# Power_Sensors.net
KiCad netlist of a schematic drawn in Altium Designer
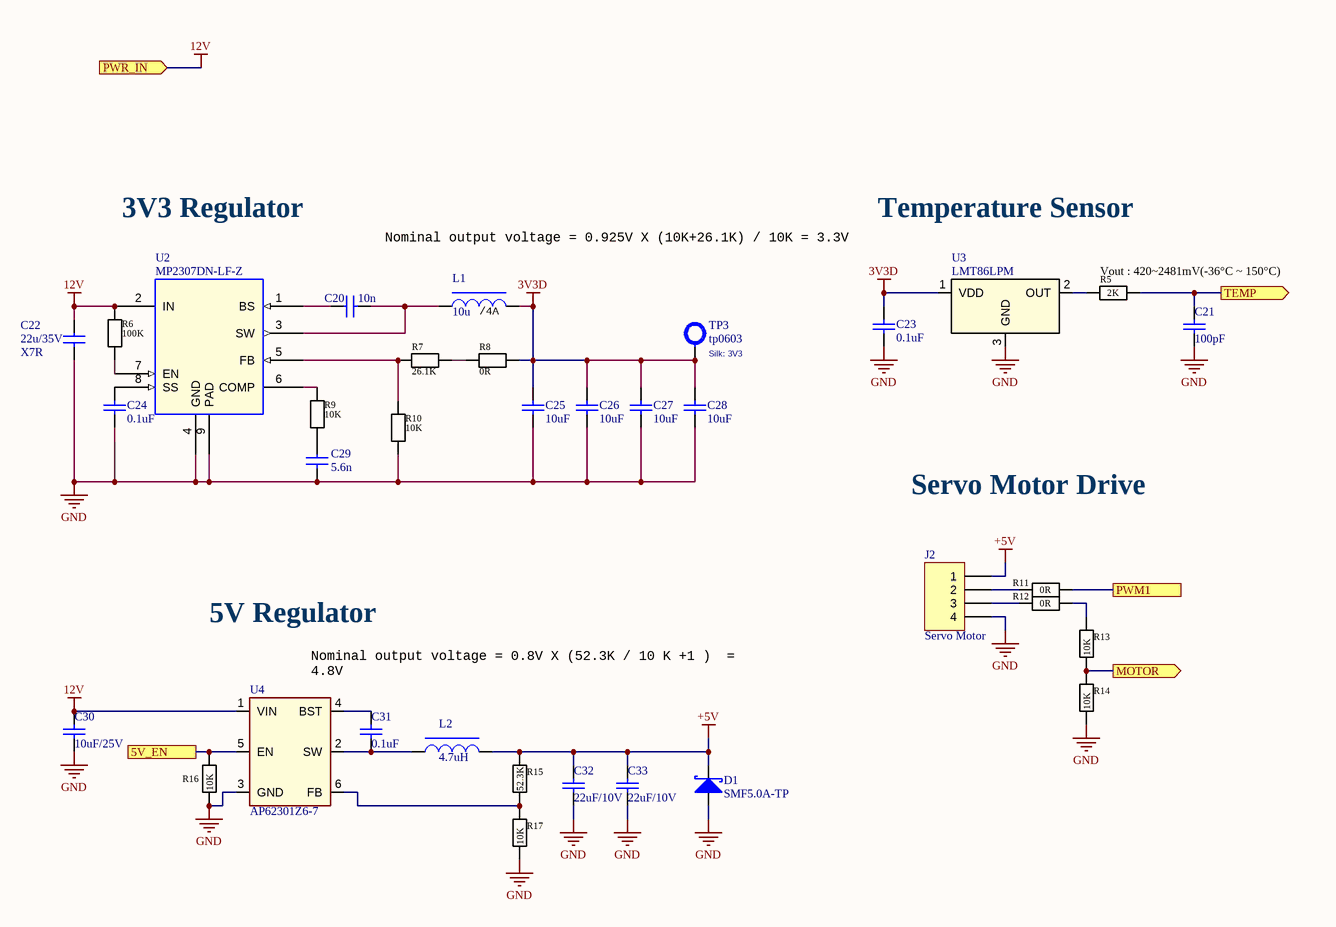
[diagram p0: Power,Sensors.SchDoc]

(export (version "E")
  (design (tool "Eeschema 10.0.6"))
  (components
    (comp (ref "C20")
      (value "10n")
      (footprint "CAPC1005X55USR")
      (description "CAP CER 10000PF 25V X7R 0402")
      (fields
        (field (name "DIGI-KEY PART NUMBER") "490-6340-2-ND")
        (field (name "MANUFACTURER") "Murata Electronics")
      )
      (libsource (lib "AA-Design-Challenge") (part "capacitor"))
    )
    (comp (ref "C21")
      (value "100pF")
      (footprint "CAPC1005X61USR")
      (description "CAP CER 100PF 50V C0G/NP0 0402")
      (fields
        (field (name "MANUFACTURER") "Murata Electronics")
        (field (name "MANUFACTURER PART NUMBER") "GCM1555C1H101FA16D")
      )
      (libsource (lib "AA-Design-Challenge") (part "Cap"))
    )
    (comp (ref "C22")
      (value "22u/35V")
      (footprint "CAPC3216X175USR")
      (description "CAP CER 22UF 35V JB 1206")
      (fields
        (field (name "MATERIAL") "X7R")
        (field (name "MANUFACTURER PART NUMBER") "C3216JB1V226M160AC")
        (field (name "MANUFACTURER") "TDK Corporation")
      )
      (libsource (lib "AA-Design-Challenge") (part "capacitor"))
    )
    (comp (ref "C23")
      (value "0.1uF")
      (footprint "CAPC1005X61USR")
      (description "CAP CER 0.1UF 50V X7R 0402")
      (fields
        (field (name "MANUFACTURER") "TDK Corporation")
        (field (name "MANUFACTURER PART NUMBER") "CGA2B3X7R1H104K050BB")
      )
      (libsource (lib "AA-Design-Challenge") (part "Cap"))
    )
    (comp (ref "C24")
      (value "0.1uF")
      (footprint "CAPC1005X61USR")
      (description "CAP CER 0.1UF 50V X7R 0402")
      (fields
        (field (name "MANUFACTURER") "TDK Corporation")
        (field (name "MANUFACTURER PART NUMBER") "CGA2B3X7R1H104K050BB")
      )
      (libsource (lib "AA-Design-Challenge") (part "Cap"))
    )
    (comp (ref "C25")
      (value "10uF")
      (footprint "CAPC1005X61USR")
      (description "CAP CER 10UF 10V X5R 0402")
      (fields
        (field (name "MANUFACTURER") "Samsung Electro-Mechanics")
        (field (name "MANUFACTURER PART NUMBER") "CL05A106MP8NUB8")
      )
      (libsource (lib "AA-Design-Challenge") (part "Cap"))
    )
    (comp (ref "C26")
      (value "10uF")
      (footprint "CAPC1005X61USR")
      (description "CAP CER 10UF 10V X5R 0402")
      (fields
        (field (name "MANUFACTURER") "Samsung Electro-Mechanics")
        (field (name "MANUFACTURER PART NUMBER") "CL05A106MP8NUB8")
      )
      (libsource (lib "AA-Design-Challenge") (part "Cap"))
    )
    (comp (ref "C27")
      (value "10uF")
      (footprint "CAPC1005X61USR")
      (description "CAP CER 10UF 10V X5R 0402")
      (fields
        (field (name "MANUFACTURER") "Samsung Electro-Mechanics")
        (field (name "MANUFACTURER PART NUMBER") "CL05A106MP8NUB8")
      )
      (libsource (lib "AA-Design-Challenge") (part "Cap"))
    )
    (comp (ref "C28")
      (value "10uF")
      (footprint "CAPC1005X61USR")
      (description "CAP CER 10UF 10V X5R 0402")
      (fields
        (field (name "MANUFACTURER") "Samsung Electro-Mechanics")
        (field (name "MANUFACTURER PART NUMBER") "CL05A106MP8NUB8")
      )
      (libsource (lib "AA-Design-Challenge") (part "Cap"))
    )
    (comp (ref "C29")
      (value "5.6n")
      (footprint "CAPC1005X55USR")
      (description "CAP CER 5600PF 50V X7R 0402")
      (fields
        (field (name "DIGI-KEY PART NUMBER") "490-6364-2-ND")
        (field (name "MANUFACTURER") "Murata Electronics")
      )
      (libsource (lib "AA-Design-Challenge") (part "capacitor"))
    )
    (comp (ref "C30")
      (value "10uF/25V")
      (footprint "CAPC2012X145USR")
      (description "CAP CER 10UF 25V X5R 0805")
      (fields
        (field (name "MANUFACTURER") "TDK Corporation")
        (field (name "MANUFACTURER PART NUMBER") "C2012X5R1E106K125AB")
      )
      (libsource (lib "AA-Design-Challenge") (part "Cap"))
    )
    (comp (ref "C31")
      (value "0.1uF")
      (footprint "CAPC1005X61USR")
      (description "CAP CER 0.1UF 50V X7R 0402")
      (fields
        (field (name "MANUFACTURER") "TDK Corporation")
        (field (name "MANUFACTURER PART NUMBER") "CGA2B3X7R1H104K050BB")
      )
      (libsource (lib "AA-Design-Challenge") (part "Cap"))
    )
    (comp (ref "C32")
      (value "22uF/10V")
      (footprint "CAPC2012X145USR")
      (description "CAP CER 22UF 10V X5R 0805")
      (fields
        (field (name "MANUFACTURER") "Samsung")
        (field (name "MANUFACTURER PART NUMBER") "CL21A226KPCLRNC")
      )
      (libsource (lib "AA-Design-Challenge") (part "Cap"))
    )
    (comp (ref "C33")
      (value "22uF/10V")
      (footprint "CAPC2012X145USR")
      (description "CAP CER 22UF 10V X5R 0805")
      (fields
        (field (name "MANUFACTURER") "Samsung")
        (field (name "MANUFACTURER PART NUMBER") "CL21A226KPCLRNC")
      )
      (libsource (lib "AA-Design-Challenge") (part "Cap"))
    )
    (comp (ref "D1")
      (value "SMF5.0A-TP")
      (footprint "SOD123FL")
      (description "TVS DIODE 5VWM 9.2VC SOD123FL")
      (fields (field (name "MANUFACTURER") "Micro Commercial Co"))
      (libsource (lib "AA-Design-Challenge") (part "SMF5.0A-TP"))
    )
    (comp (ref "J2")
      (value "Servo Motor")
      (footprint "4 pin 2.54 mm Breakaway")
      (description "Header, 4-Pin")
      (libsource (lib "AA-Design-Challenge") (part "Header 4"))
    )
    (comp (ref "L1")
      (value "10u")
      (footprint "IND_0630CDMCCDS_SUM")
      (description "FIXED IND 10UH 4A 67 MOHM SMD")
      (fields (field (name "DIGI-KEY PART NUMBER") "308-2459-2-ND") (field (name "VOLTAGE") "V"))
      (libsource (lib "AA-Design-Challenge") (part "inductor"))
    )
    (comp (ref "L2")
      (value "4.7uH")
      (footprint "IND_NR5040")
      (description "FIXED IND 4.7UH 3.1A 37.7MOHM SM")
      (fields
        (field (name "DIGI-KEY PART NUMBER") "587-2373-2-ND")
        (field (name "MANUFACTURER") "Taiyo Yuden")
      )
      (libsource (lib "AA-Design-Challenge") (part "inductor"))
    )
    (comp (ref "R5")
      (value "2K")
      (footprint "RESC1005X40USR")
      (description "RES SMD 2K OHM 1% 1/16W 0402")
      (fields
        (field (name "MANUFACTURER") "Yageo")
        (field (name "MANUFACTURER PART NUMBER") "RC0402FR-072KL")
      )
      (libsource (lib "AA-Design-Challenge") (part "R"))
    )
    (comp (ref "R6")
      (value "100K")
      (footprint "RESC1005X40USR")
      (description "RES SMD 100K OHM 1% 1/16W 0402")
      (fields
        (field (name "MANUFACTURER") "Yageo")
        (field (name "MANUFACTURER PART NUMBER") "RC0402FR-07100KL")
      )
      (libsource (lib "") (part "R_2"))
    )
    (comp (ref "R7")
      (value "26.1K")
      (footprint "RESC1005X40USR")
      (description "RES SMD 26.1K OHM 1% 1/5W 0402")
      (fields
        (field (name "MANUFACTURER") "Vishay Dale")
        (field (name "MANUFACTURER PART NUMBER") "CRCW040226K1FKEDHP")
      )
      (libsource (lib "AA-Design-Challenge") (part "R"))
    )
    (comp (ref "R8")
      (value "0R")
      (footprint "RESC1005X40USR")
      (description "RES SMD 0 OHM JUMPER 1/16W 0402")
      (fields
        (field (name "MANUFACTURER") "Yageo")
        (field (name "MANUFACTURER PART NUMBER") "RC0402FR-070RL")
      )
      (libsource (lib "AA-Design-Challenge") (part "R"))
    )
    (comp (ref "R9")
      (value "10K")
      (footprint "RESC1005X40USR")
      (description "RES 10K OHM 1% 1/16W 0402")
      (fields
        (field (name "MANUFACTURER") "Stackpole Electronics Inc")
        (field (name "MANUFACTURER PART NUMBER") "RMCF0402FT10K0")
      )
      (libsource (lib "") (part "R_2"))
    )
    (comp (ref "R10")
      (value "10K")
      (footprint "RESC1005X40USR")
      (description "RES 10K OHM 1% 1/16W 0402")
      (fields
        (field (name "MANUFACTURER") "Stackpole Electronics Inc")
        (field (name "MANUFACTURER PART NUMBER") "RMCF0402FT10K0")
      )
      (libsource (lib "") (part "R_2"))
    )
    (comp (ref "R11")
      (value "0R")
      (footprint "RESC1005X40USR")
      (description "RES SMD 0 OHM JUMPER 1/16W 0402")
      (fields
        (field (name "MANUFACTURER") "Yageo")
        (field (name "MANUFACTURER PART NUMBER") "RC0402FR-070RL")
      )
      (libsource (lib "AA-Design-Challenge") (part "R"))
    )
    (comp (ref "R12")
      (value "0R")
      (footprint "RESC1005X40USR")
      (description "RES SMD 0 OHM JUMPER 1/16W 0402")
      (fields
        (field (name "MANUFACTURER") "Yageo")
        (field (name "MANUFACTURER PART NUMBER") "RC0402FR-070RL")
      )
      (libsource (lib "AA-Design-Challenge") (part "R"))
    )
    (comp (ref "R13")
      (value "10K")
      (footprint "RESC1005X40USR")
      (description "RES SMD 10K OHM 1% 1/16W 0402")
      (fields
        (field (name "MANUFACTURER") "Yageo")
        (field (name "DISTRIBUTOR PART NUMBER") "311-10.0KLRTR-ND")
      )
      (libsource (lib "") (part "R_1"))
    )
    (comp (ref "R14")
      (value "10K")
      (footprint "RESC1005X40USR")
      (description "RES SMD 10K OHM 1% 1/16W 0402")
      (fields
        (field (name "MANUFACTURER") "Yageo")
        (field (name "DISTRIBUTOR PART NUMBER") "311-10.0KLRTR-ND")
      )
      (libsource (lib "") (part "R_1"))
    )
    (comp (ref "R15")
      (value "52.3K")
      (footprint "RESC1005X40USR")
      (description "RES SMD 52.3K OHM 1% 1/16W 0402")
      (fields
        (field (name "MANUFACTURER") "Yageo")
        (field (name "MANUFACTURER PART NUMBER") "RC0402FR-0752K3L")
      )
      (libsource (lib "") (part "R_1"))
    )
    (comp (ref "R16")
      (value "10K")
      (footprint "RESC1005X40USR")
      (description "RES SMD 10K OHM 1% 1/16W 0402")
      (fields
        (field (name "MANUFACTURER") "Yageo")
        (field (name "MANUFACTURER PART NUMBER") "RC0402FR-0710KL")
      )
      (libsource (lib "") (part "R_1"))
    )
    (comp (ref "R17")
      (value "10K")
      (footprint "RESC1005X40USR")
      (description "RES SMD 10K OHM 1% 1/16W 0402")
      (fields
        (field (name "MANUFACTURER") "Yageo")
        (field (name "MANUFACTURER PART NUMBER") "RC0402FR-0710KL")
      )
      (libsource (lib "") (part "R_1"))
    )
    (comp (ref "TP3")
      (value "tp0603")
      (footprint "TP 1mm")
      (fields (field (name "SILK") "3V3") (field (name "PART NUMBER") "4001364"))
      (libsource (lib "AA-Design-Challenge") (part "Testpkt0603"))
    )
    (comp (ref "U2")
      (value "MP2307DN-LF-Z")
      (footprint "SOIC127P600X175-9N")
      (description "IC REG BUCK ADJUSTABLE 3A 8SOIC")
      (fields
        (field (name "DIGI-KEY PART NUMBER") "1589-1576-2-ND")
        (field (name "MANUFACTURER") "Monolithic Power Systems Inc.")
      )
      (libsource (lib "AA-Design-Challenge") (part "MP2307"))
    )
    (comp (ref "U3")
      (value "LMT86LPM")
      (footprint "LP3_TEX")
      (description "SENSOR ANALOG -50C-150C TO92-3")
      (fields
        (field (name "MANUFACTURER") "Texas Instruments")
        (field (name "DIGI-KEY PART NUMBER") "296-46127-1-ND")
        (field (name "COPYRIGHT") "Copyright (C) 2018 Accelerated Designs. All rights reserved")
      )
      (libsource (lib "AA-Design-Challenge") (part "LMT86LPM"))
    )
    (comp (ref "U4")
      (value "AP62301Z6-7")
      (footprint "SOT563")
      (description "DCDC CONV HV BUCK SOT563 T&R 3K")
      (fields
        (field (name "MANUFACTURER") "Diodes Incorporated")
        (field (name "DIGI-KEY PART NUMBER") "31-AP62301Z6-7TR-ND")
      )
      (libsource (lib "AA-Design-Challenge") (part "TPS563207SDRLR"))
    )
  )
  (nets
    (net (code "1") (name "+5V") (class "Default")
      (node (ref "C32") (pin "1") (pinfunction "1_1") (pintype "passive"))
      (node (ref "C33") (pin "1") (pinfunction "1_1") (pintype "passive"))
      (node (ref "D1") (pin "C") (pinfunction "C_C") (pintype "passive"))
      (node (ref "J2") (pin "1") (pinfunction "1_1") (pintype "passive"))
      (node (ref "L2") (pin "2") (pinfunction "2_2") (pintype "passive"))
      (node (ref "R15") (pin "2") (pintype "passive"))
    )
    (net (code "2") (name "/5V_EN") (class "Default")
      (node (ref "R16") (pin "2") (pintype "passive"))
      (node (ref "U4") (pin "5") (pinfunction "EN_5") (pintype "passive"))
    )
    (net (code "3") (name "/MOTOR") (class "Default")
      (node (ref "R13") (pin "1") (pintype "passive"))
      (node (ref "R14") (pin "2") (pintype "passive"))
    )
    (net (code "4") (name "/PWM1") (class "Default") (node (ref "R11") (pin "2") (pintype "passive")))
    (net (code "5") (name "/TEMP") (class "Default")
      (node (ref "C21") (pin "2") (pinfunction "2_2") (pintype "passive"))
      (node (ref "R5") (pin "2") (pintype "passive"))
    )
    (net (code "6") (name "3V3D") (class "Default")
      (node (ref "C23") (pin "1") (pinfunction "1_1") (pintype "passive"))
      (node (ref "C25") (pin "1") (pinfunction "1_1") (pintype "passive"))
      (node (ref "C26") (pin "1") (pinfunction "1_1") (pintype "passive"))
      (node (ref "C27") (pin "1") (pinfunction "1_1") (pintype "passive"))
      (node (ref "C28") (pin "1") (pinfunction "1_1") (pintype "passive"))
      (node (ref "L1") (pin "2") (pinfunction "2_2") (pintype "passive"))
      (node (ref "R8") (pin "2") (pintype "passive"))
      (node (ref "TP3") (pin "1") (pinfunction "1_1") (pintype "passive"))
      (node (ref "U3") (pin "1") (pinfunction "VDD_1") (pintype "passive"))
    )
    (net (code "7") (name "12V") (class "Default")
      (node (ref "C22") (pin "1") (pinfunction "1_1") (pintype "passive"))
      (node (ref "C30") (pin "1") (pinfunction "1_1") (pintype "passive"))
      (node (ref "R6") (pin "1") (pintype "passive"))
      (node (ref "U2") (pin "2") (pinfunction "IN_2") (pintype "power_in"))
      (node (ref "U4") (pin "1") (pinfunction "VIN_1") (pintype "passive"))
    )
    (net (code "8") (name "GND") (class "Default")
      (node (ref "C21") (pin "1") (pinfunction "1_1") (pintype "passive"))
      (node (ref "C22") (pin "2") (pinfunction "2_2") (pintype "passive"))
      (node (ref "C23") (pin "2") (pinfunction "2_2") (pintype "passive"))
      (node (ref "C24") (pin "2") (pinfunction "2_2") (pintype "passive"))
      (node (ref "C25") (pin "2") (pinfunction "2_2") (pintype "passive"))
      (node (ref "C26") (pin "2") (pinfunction "2_2") (pintype "passive"))
      (node (ref "C27") (pin "2") (pinfunction "2_2") (pintype "passive"))
      (node (ref "C28") (pin "2") (pinfunction "2_2") (pintype "passive"))
      (node (ref "C29") (pin "2") (pinfunction "2_2") (pintype "passive"))
      (node (ref "C30") (pin "2") (pinfunction "2_2") (pintype "passive"))
      (node (ref "C32") (pin "2") (pinfunction "2_2") (pintype "passive"))
      (node (ref "C33") (pin "2") (pinfunction "2_2") (pintype "passive"))
      (node (ref "D1") (pin "A") (pinfunction "A_A") (pintype "passive"))
      (node (ref "J2") (pin "4") (pinfunction "4_4") (pintype "passive"))
      (node (ref "R10") (pin "2") (pintype "passive"))
      (node (ref "R14") (pin "1") (pintype "passive"))
      (node (ref "R16") (pin "1") (pintype "passive"))
      (node (ref "R17") (pin "1") (pintype "passive"))
      (node (ref "U2") (pin "4") (pinfunction "GND_4") (pintype "power_in"))
      (node (ref "U2") (pin "9") (pinfunction "PAD_9") (pintype "power_in"))
      (node (ref "U3") (pin "3") (pinfunction "GND_3") (pintype "passive"))
      (node (ref "U4") (pin "3") (pinfunction "GND_3") (pintype "passive"))
    )
    (net (code "9") (name "Net-(C29-Pad1)") (class "Default")
      (node (ref "C29") (pin "1") (pinfunction "1_1") (pintype "passive"))
      (node (ref "R9") (pin "2") (pintype "passive"))
    )
    (net (code "10") (name "Net-(J2-Pad2)") (class "Default")
      (node (ref "J2") (pin "2") (pinfunction "2_2") (pintype "passive"))
      (node (ref "R11") (pin "1") (pintype "passive"))
    )
    (net (code "11") (name "Net-(J2-Pad3)") (class "Default")
      (node (ref "J2") (pin "3") (pinfunction "3_3") (pintype "passive"))
      (node (ref "R12") (pin "1") (pintype "passive"))
    )
    (net (code "12") (name "Net-(R7-Pad2)") (class "Default")
      (node (ref "R7") (pin "2") (pintype "passive"))
      (node (ref "R8") (pin "1") (pintype "passive"))
    )
    (net (code "13") (name "Net-(R12-Pad2)") (class "Default")
      (node (ref "R12") (pin "2") (pintype "passive"))
      (node (ref "R13") (pin "2") (pintype "passive"))
    )
    (net (code "14") (name "Net-(U2-BS)") (class "Default")
      (node (ref "C20") (pin "1") (pinfunction "1_1") (pintype "passive"))
      (node (ref "U2") (pin "1") (pinfunction "BS_1") (pintype "input"))
    )
    (net (code "15") (name "Net-(U2-COMP)") (class "Default")
      (node (ref "R9") (pin "1") (pintype "passive"))
      (node (ref "U2") (pin "6") (pinfunction "COMP_6") (pintype "passive"))
    )
    (net (code "16") (name "Net-(U2-EN)") (class "Default")
      (node (ref "R6") (pin "2") (pintype "passive"))
      (node (ref "U2") (pin "7") (pinfunction "EN_7") (pintype "input"))
    )
    (net (code "17") (name "Net-(U2-FB)") (class "Default")
      (node (ref "R10") (pin "1") (pintype "passive"))
      (node (ref "R7") (pin "1") (pintype "passive"))
      (node (ref "U2") (pin "5") (pinfunction "FB_5") (pintype "input"))
    )
    (net (code "18") (name "Net-(U2-SS)") (class "Default")
      (node (ref "C24") (pin "1") (pinfunction "1_1") (pintype "passive"))
      (node (ref "U2") (pin "8") (pinfunction "SS_8") (pintype "input"))
    )
    (net (code "19") (name "Net-(U2-SW)") (class "Default")
      (node (ref "C20") (pin "2") (pinfunction "2_2") (pintype "passive"))
      (node (ref "L1") (pin "1") (pinfunction "1_1") (pintype "passive"))
      (node (ref "U2") (pin "3") (pinfunction "SW_3") (pintype "output"))
    )
    (net (code "20") (name "Net-(U3-OUT)") (class "Default")
      (node (ref "R5") (pin "1") (pintype "passive"))
      (node (ref "U3") (pin "2") (pinfunction "OUT_2") (pintype "passive"))
    )
    (net (code "21") (name "Net-(U4-BST)") (class "Default")
      (node (ref "C31") (pin "1") (pinfunction "1_1") (pintype "passive"))
      (node (ref "U4") (pin "4") (pinfunction "BST_4") (pintype "passive"))
    )
    (net (code "22") (name "Net-(U4-FB)") (class "Default")
      (node (ref "R15") (pin "1") (pintype "passive"))
      (node (ref "R17") (pin "2") (pintype "passive"))
      (node (ref "U4") (pin "6") (pinfunction "FB_6") (pintype "passive"))
    )
    (net (code "23") (name "Net-(U4-SW)") (class "Default")
      (node (ref "C31") (pin "2") (pinfunction "2_2") (pintype "passive"))
      (node (ref "L2") (pin "1") (pinfunction "1_1") (pintype "passive"))
      (node (ref "U4") (pin "2") (pinfunction "SW_2") (pintype "passive"))
    )
  )
)
